# atiny13u-breakout.net
KiCad netlist of a schematic drawn in EAGLE
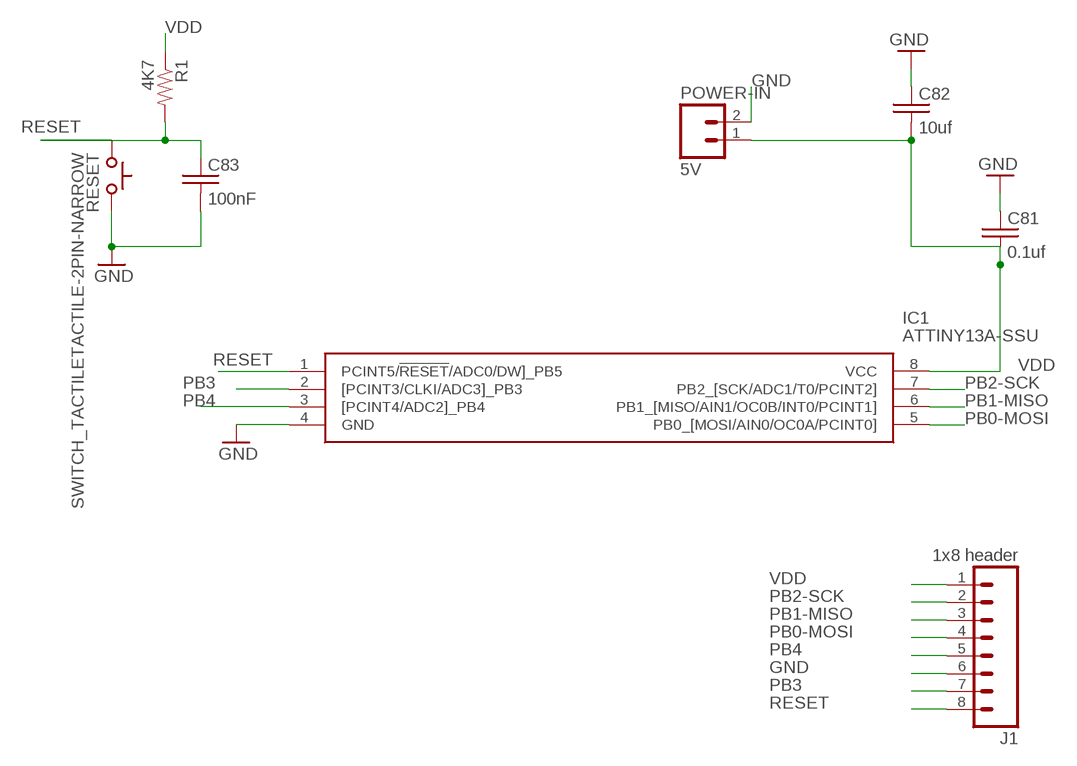
[diagram p0: schematic, sheet 1]

(export (version "E")
  (design (tool "Eeschema 10.0.6"))
  (components
    (comp (ref "C81")
      (value "0.1uf")
      (footprint "eagle-import:C0805-VOLTA")
      (libsource (lib "eagle-import") (part "C-USC0805-VOLTERA"))
    )
    (comp (ref "C82")
      (value "10uf")
      (footprint "eagle-import:C0805-VOLTA")
      (libsource (lib "eagle-import") (part "C-USC0805-VOLTERA"))
    )
    (comp (ref "C83")
      (value "100nF")
      (footprint "eagle-import:C0805-VOLTA")
      (libsource (lib "eagle-import") (part "C-USC0805-VOLTERA"))
    )
    (comp (ref "IC1")
      (value "ATTINY13A-SSU")
      (footprint "eagle-import:SOIC127P600X175-8N")
      (fields (field (name "RS_PART_NUMBER") "9214573"))
      (libsource (lib "eagle-import") (part "ATTINY13A-SSU"))
    )
    (comp (ref "J1")
      (value "1x8 header")
      (footprint "eagle-import:1X08")
      (libsource (lib "eagle-import") (part "M08SILK_FEMALE_PTH"))
    )
    (comp (ref "POWER-IN")
      (value "5V")
      (footprint "eagle-import:1X02")
      (libsource (lib "eagle-import") (part "M02PTH"))
    )
    (comp (ref "R1")
      (value "4K7")
      (footprint "eagle-import:0805")
      (libsource (lib "eagle-import") (part "RESISTOR0805-RES"))
    )
    (comp (ref "RESET")
      (value "SWITCH_TACTILETACTILE-2PIN-NARROW")
      (footprint "eagle-import:TACTILE-2PIN-NARROW")
      (libsource (lib "eagle-import") (part "SWITCH_TACTILETACTILE-2PIN-NARROW"))
    )
  )
  (nets
    (net (code "1") (name "/PB0-MOSI") (class "Default")
      (node (ref "IC1") (pin "5") (pinfunction "PB0_[MOSI/AIN0/OC0A/PCINT0]_5") (pintype "input"))
      (node (ref "J1") (pin "4") (pinfunction "4_4") (pintype "passive"))
    )
    (net (code "2") (name "/PB1-MISO") (class "Default")
      (node (ref "IC1") (pin "6") (pinfunction "PB1_[MISO/AIN1/OC0B/INT0/PCINT1]_6") (pintype "input"))
      (node (ref "J1") (pin "3") (pinfunction "3_3") (pintype "passive"))
    )
    (net (code "3") (name "/PB2-SCK") (class "Default")
      (node (ref "IC1") (pin "7") (pinfunction "PB2_[SCK/ADC1/T0/PCINT2]_7") (pintype "input"))
      (node (ref "J1") (pin "2") (pinfunction "2_2") (pintype "passive"))
    )
    (net (code "4") (name "/PB3") (class "Default")
      (node (ref "IC1") (pin "2") (pinfunction "[PCINT3/CLKI/ADC3]_PB3_2") (pintype "input"))
      (node (ref "J1") (pin "7") (pinfunction "7_7") (pintype "passive"))
    )
    (net (code "5") (name "/PB4") (class "Default")
      (node (ref "IC1") (pin "3") (pinfunction "[PCINT4/ADC2]_PB4_3") (pintype "input"))
      (node (ref "J1") (pin "5") (pinfunction "5_5") (pintype "passive"))
    )
    (net (code "6") (name "/RESET") (class "Default")
      (node (ref "C83") (pin "1") (pinfunction "1_1") (pintype "passive"))
      (node (ref "IC1") (pin "1") (pinfunction "PCINT5/~{RESET}/ADC0/DW]_PB5_1") (pintype "input"))
      (node (ref "J1") (pin "8") (pinfunction "8_8") (pintype "passive"))
      (node (ref "R1") (pin "2") (pinfunction "2_2") (pintype "passive"))
      (node (ref "RESET") (pin "P$2") (pinfunction "C_P$2") (pintype "passive"))
    )
    (net (code "7") (name "/VDD") (class "Default")
      (node (ref "C81") (pin "2") (pinfunction "2_2") (pintype "passive"))
      (node (ref "C82") (pin "2") (pinfunction "2_2") (pintype "passive"))
      (node (ref "IC1") (pin "8") (pinfunction "VCC_8") (pintype "power_in"))
      (node (ref "J1") (pin "1") (pinfunction "1_1") (pintype "passive"))
      (node (ref "POWER-IN") (pin "1") (pinfunction "1_1") (pintype "passive"))
      (node (ref "R1") (pin "1") (pinfunction "1_1") (pintype "passive"))
    )
    (net (code "8") (name "GND") (class "Default")
      (node (ref "C81") (pin "1") (pinfunction "1_1") (pintype "passive"))
      (node (ref "C82") (pin "1") (pinfunction "1_1") (pintype "passive"))
      (node (ref "C83") (pin "2") (pinfunction "2_2") (pintype "passive"))
      (node (ref "IC1") (pin "4") (pinfunction "GND_4") (pintype "power_in"))
      (node (ref "J1") (pin "6") (pinfunction "6_6") (pintype "passive"))
      (node (ref "POWER-IN") (pin "2") (pinfunction "2_2") (pintype "passive"))
      (node (ref "RESET") (pin "P$1") (pinfunction "A_P$1") (pintype "passive"))
    )
  )
)
